# main.net
KiCad netlist of a schematic drawn in Altium Designer
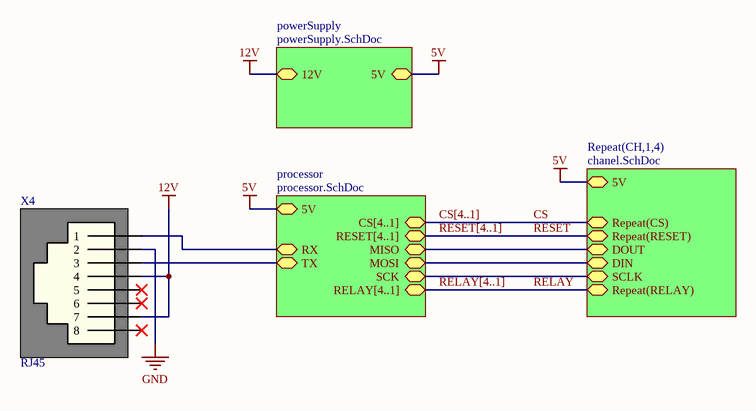
[diagram p0: main.SchDoc]

(export (version "E")
  (design (tool "Eeschema 10.0.6"))
  (components
    (comp (ref "X4")
      (value "RJ45")
      (footprint "RJ45")
      (description "Outlet YH-55-05 8P8C 5521")
      (libsource (lib "SmartOutletIntegratedLibrary") (part "RJ45"))
    )
  )
  (nets
    (net (code "21") (name "/RX") (class "Default")
      (node (ref "X4") (pin "1") (pinfunction "1_1") (pintype "passive"))
    )
    (net (code "23") (name "/TX") (class "Default")
      (node (ref "X4") (pin "3") (pinfunction "3_3") (pintype "passive"))
    )
    (net (code "25") (name "12V") (class "Default")
      (node (ref "X4") (pin "4") (pinfunction "4_4") (pintype "passive"))
      (node (ref "X4") (pin "7") (pinfunction "7_7") (pintype "passive"))
    )
    (net (code "26") (name "GND") (class "Default")
      (node (ref "X4") (pin "2") (pinfunction "2_2") (pintype "passive"))
    )
    (net (code "27") (name "unconnected-(X4-Pad5)") (class "Default")
      (node (ref "X4") (pin "5") (pinfunction "5_5") (pintype "passive+no_connect"))
    )
    (net (code "28") (name "unconnected-(X4-Pad6)") (class "Default")
      (node (ref "X4") (pin "6") (pinfunction "6_6") (pintype "passive+no_connect"))
    )
    (net (code "29") (name "unconnected-(X4-Pad8)") (class "Default")
      (node (ref "X4") (pin "8") (pinfunction "8_8") (pintype "passive+no_connect"))
    )
  )
)
